# novice_shield_v1.net
KiCad netlist of a schematic drawn in EAGLE
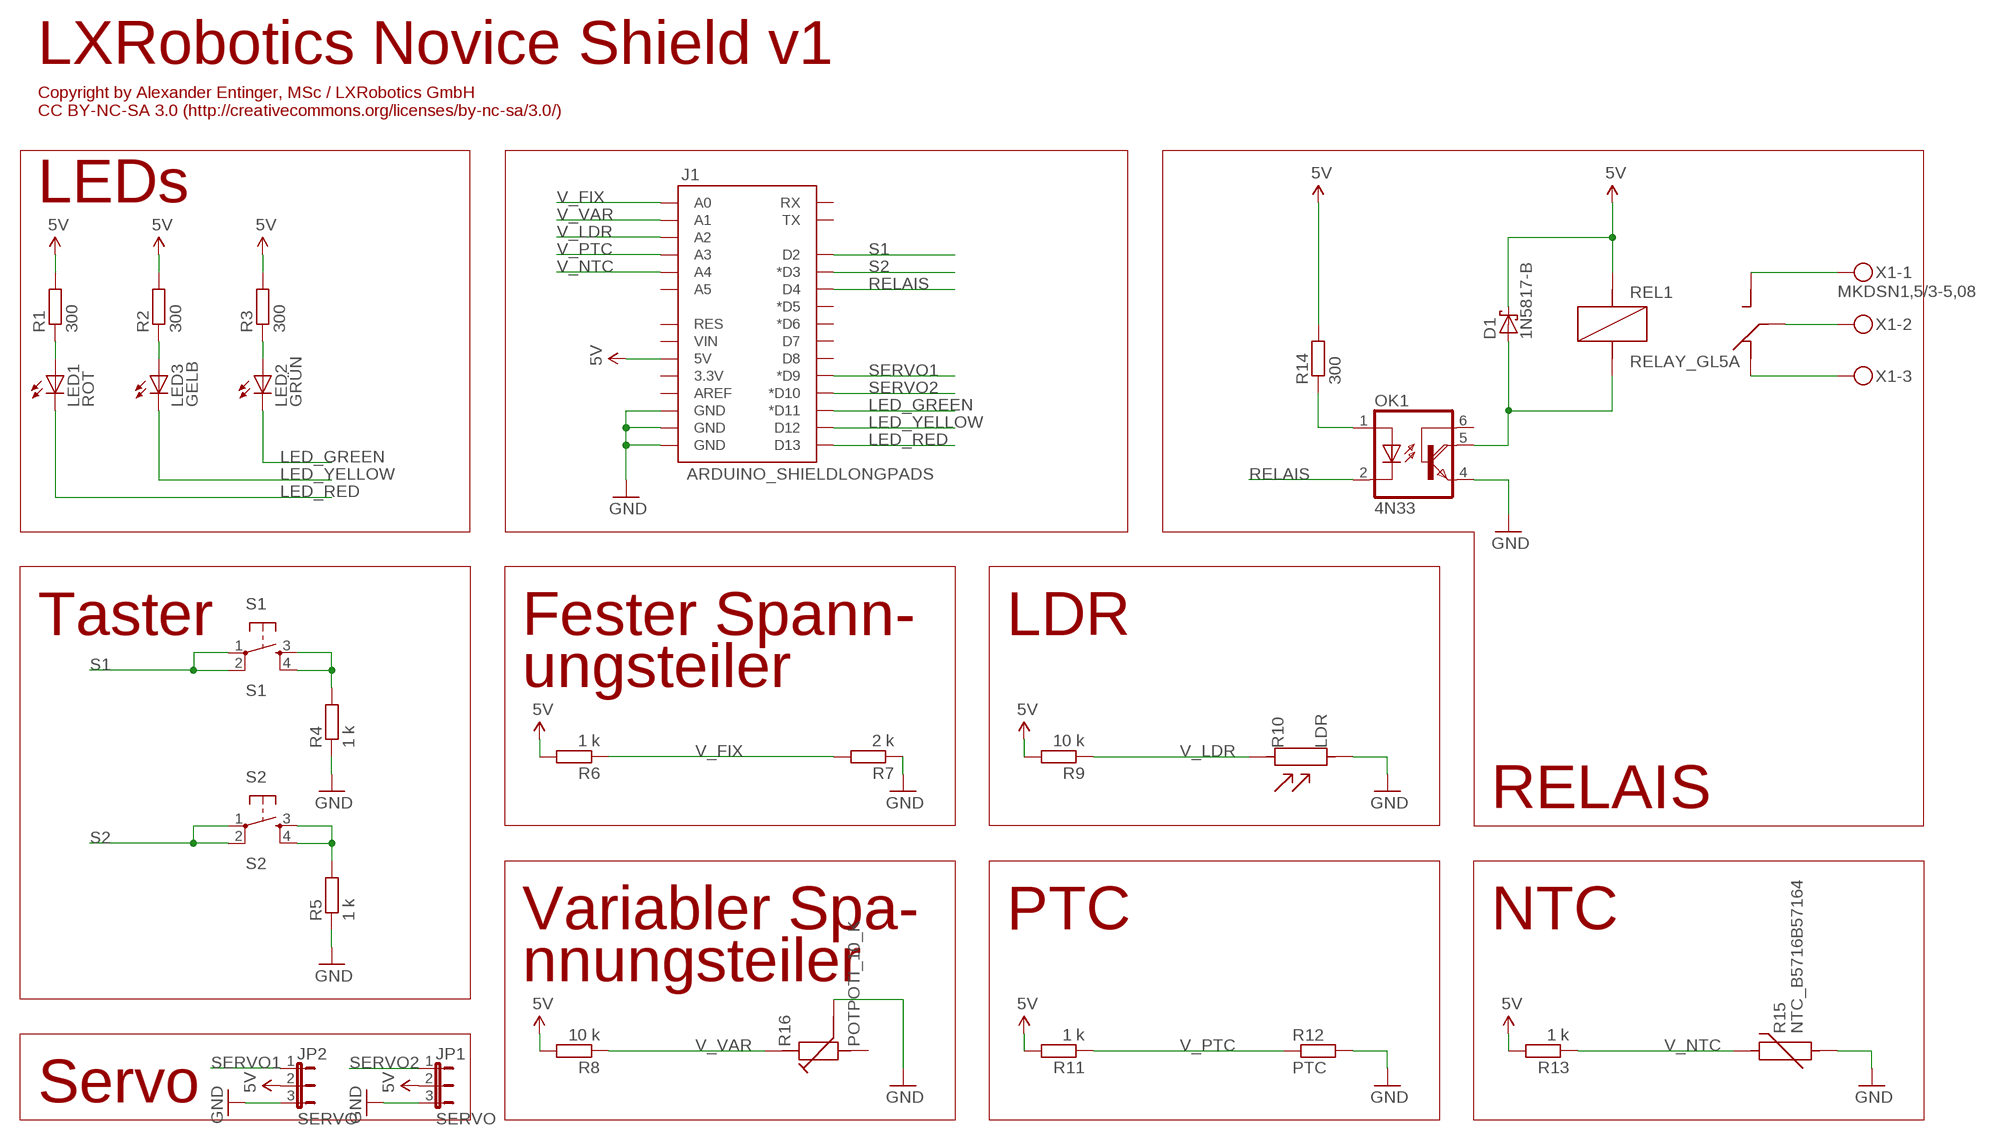
[diagram p0: schematic, sheet 1]

(export (version "E")
  (design (tool "Eeschema 10.0.6"))
  (components
    (comp (ref "D1")
      (value "1N5817-B")
      (footprint "eagle-import:DO41-7.6")
      (libsource (lib "eagle-import") (part "1N5817-B"))
    )
    (comp (ref "J1")
      (value "ARDUINO_SHIELDLONGPADS")
      (footprint "eagle-import:DUEMILANOVE_SHIELD_LONGPADS")
      (libsource (lib "eagle-import") (part "ARDUINO_SHIELDLONGPADS"))
    )
    (comp (ref "JP1")
      (value "SERVO")
      (footprint "eagle-import:JP2")
      (libsource (lib "eagle-import") (part "JP2E"))
    )
    (comp (ref "JP2")
      (value "SERVO")
      (footprint "eagle-import:JP2")
      (libsource (lib "eagle-import") (part "JP2E"))
    )
    (comp (ref "LED1")
      (value "ROT")
      (footprint "eagle-import:LED5MM")
      (libsource (lib "eagle-import") (part "LED5MM"))
    )
    (comp (ref "LED2")
      (value "GRÜN")
      (footprint "eagle-import:LED5MM")
      (libsource (lib "eagle-import") (part "LED5MM"))
    )
    (comp (ref "LED3")
      (value "GELB")
      (footprint "eagle-import:LED5MM")
      (libsource (lib "eagle-import") (part "LED5MM"))
    )
    (comp (ref "OK1")
      (value "4N33")
      (footprint "eagle-import:DIL06")
      (fields (field (name "MF") "VISHAY/TELEFUNKEN"))
      (libsource (lib "eagle-import") (part "4N33"))
    )
    (comp (ref "R1")
      (value "300")
      (footprint "eagle-import:0204_5")
      (libsource (lib "eagle-import") (part "R-EU_0204/5"))
    )
    (comp (ref "R2")
      (value "300")
      (footprint "eagle-import:0204_5")
      (libsource (lib "eagle-import") (part "R-EU_0204/5"))
    )
    (comp (ref "R3")
      (value "300")
      (footprint "eagle-import:0204_5")
      (libsource (lib "eagle-import") (part "R-EU_0204/5"))
    )
    (comp (ref "R4")
      (value "1 k")
      (footprint "eagle-import:0204_5")
      (libsource (lib "eagle-import") (part "R-EU_0204/5"))
    )
    (comp (ref "R5")
      (value "1 k")
      (footprint "eagle-import:0204_5")
      (libsource (lib "eagle-import") (part "R-EU_0204/5"))
    )
    (comp (ref "R6")
      (value "1 k")
      (footprint "eagle-import:0204_5")
      (libsource (lib "eagle-import") (part "R-EU_0204/5"))
    )
    (comp (ref "R7")
      (value "2 k")
      (footprint "eagle-import:0204_5")
      (libsource (lib "eagle-import") (part "R-EU_0204/5"))
    )
    (comp (ref "R8")
      (value "10 k")
      (footprint "eagle-import:0204_5")
      (libsource (lib "eagle-import") (part "R-EU_0204/5"))
    )
    (comp (ref "R9")
      (value "10 k")
      (footprint "eagle-import:0204_5")
      (libsource (lib "eagle-import") (part "R-EU_0204/5"))
    )
    (comp (ref "R10")
      (value "LDR")
      (footprint "eagle-import:LDR")
      (libsource (lib "eagle-import") (part "LDR"))
    )
    (comp (ref "R11")
      (value "1 k")
      (footprint "eagle-import:0204_5")
      (libsource (lib "eagle-import") (part "R-EU_0204/5"))
    )
    (comp (ref "R12")
      (value "PTC")
      (footprint "eagle-import:0207_10")
      (libsource (lib "eagle-import") (part "R-EU_0207/10"))
    )
    (comp (ref "R13")
      (value "1 k")
      (footprint "eagle-import:0204_5")
      (libsource (lib "eagle-import") (part "R-EU_0204/5"))
    )
    (comp (ref "R14")
      (value "300")
      (footprint "eagle-import:0204_5")
      (libsource (lib "eagle-import") (part "R-EU_0204/5"))
    )
    (comp (ref "R15")
      (value "NTC_B5716B57164")
      (footprint "eagle-import:NTC_5MM_RADIAL")
      (libsource (lib "eagle-import") (part "NTC_B5716B57164"))
    )
    (comp (ref "R16")
      (value "POTPOTI_10_K")
      (footprint "eagle-import:POT_10K")
      (libsource (lib "eagle-import") (part "POTPOTI_10_K"))
    )
    (comp (ref "REL1")
      (value "RELAY_GL5A")
      (footprint "eagle-import:RELAY_GL5A")
      (libsource (lib "eagle-import") (part "RELAY_GL5A"))
    )
    (comp (ref "S1")
      (value "S1")
      (footprint "eagle-import:TACTILE-PTH")
      (libsource (lib "eagle-import") (part "TAC_SWITCHPTH"))
    )
    (comp (ref "S2")
      (value "S2")
      (footprint "eagle-import:TACTILE-PTH")
      (libsource (lib "eagle-import") (part "TAC_SWITCHPTH"))
    )
    (comp (ref "X1")
      (value "MKDSN1,5/3-5,08")
      (footprint "eagle-import:MKDSN1,5_3-5,08")
      (fields (field (name "MPN") "SMKDSN1,5/3-5,08"))
      (libsource (lib "eagle-import") (part "MKDSN1,5/3-5,08"))
    )
  )
  (nets
    (net (code "1") (name "/LED_GREEN") (class "Default")
      (node (ref "J1") (pin "D11") (pinfunction "*D11_D11") (pintype "bidirectional"))
      (node (ref "LED2") (pin "K") (pinfunction "C_K") (pintype "passive"))
    )
    (net (code "2") (name "/LED_RED") (class "Default")
      (node (ref "J1") (pin "D13") (pinfunction "D13_D13") (pintype "bidirectional"))
      (node (ref "LED1") (pin "K") (pinfunction "C_K") (pintype "passive"))
    )
    (net (code "3") (name "/LED_YELLOW") (class "Default")
      (node (ref "J1") (pin "D12") (pinfunction "D12_D12") (pintype "bidirectional"))
      (node (ref "LED3") (pin "K") (pinfunction "C_K") (pintype "passive"))
    )
    (net (code "4") (name "/RELAIS") (class "Default")
      (node (ref "J1") (pin "D4") (pinfunction "D4_D4") (pintype "bidirectional"))
      (node (ref "OK1") (pin "2") (pinfunction "C_2") (pintype "passive"))
    )
    (net (code "5") (name "/S1") (class "Default")
      (node (ref "J1") (pin "D2") (pinfunction "D2_D2") (pintype "bidirectional"))
      (node (ref "S1") (pin "1") (pinfunction "1_1") (pintype "passive"))
      (node (ref "S1") (pin "2") (pinfunction "2_2") (pintype "passive"))
    )
    (net (code "6") (name "/S2") (class "Default")
      (node (ref "J1") (pin "D3") (pinfunction "*D3_D3") (pintype "bidirectional"))
      (node (ref "S2") (pin "1") (pinfunction "1_1") (pintype "passive"))
      (node (ref "S2") (pin "2") (pinfunction "2_2") (pintype "passive"))
    )
    (net (code "7") (name "/SERVO1") (class "Default")
      (node (ref "J1") (pin "D9") (pinfunction "*D9_D9") (pintype "bidirectional"))
      (node (ref "JP2") (pin "1") (pinfunction "1_1") (pintype "passive"))
    )
    (net (code "8") (name "/SERVO2") (class "Default")
      (node (ref "J1") (pin "D10") (pinfunction "*D10_D10") (pintype "bidirectional"))
      (node (ref "JP1") (pin "1") (pinfunction "1_1") (pintype "passive"))
    )
    (net (code "9") (name "/V_FIX") (class "Default")
      (node (ref "J1") (pin "A0") (pinfunction "A0_A0") (pintype "bidirectional"))
      (node (ref "R6") (pin "1") (pinfunction "1_1") (pintype "passive"))
      (node (ref "R7") (pin "2") (pinfunction "2_2") (pintype "passive"))
    )
    (net (code "10") (name "/V_LDR") (class "Default")
      (node (ref "J1") (pin "A2") (pinfunction "A2_A2") (pintype "bidirectional"))
      (node (ref "R10") (pin "P$1") (pinfunction "P$1_P$1") (pintype "bidirectional"))
      (node (ref "R9") (pin "1") (pinfunction "1_1") (pintype "passive"))
    )
    (net (code "11") (name "/V_NTC") (class "Default")
      (node (ref "J1") (pin "A4") (pinfunction "A4_A4") (pintype "bidirectional"))
      (node (ref "R13") (pin "1") (pinfunction "1_1") (pintype "passive"))
      (node (ref "R15") (pin "P$1") (pinfunction "1_P$1") (pintype "bidirectional"))
    )
    (net (code "12") (name "/V_PTC") (class "Default")
      (node (ref "J1") (pin "A3") (pinfunction "A3_A3") (pintype "bidirectional"))
      (node (ref "R11") (pin "1") (pinfunction "1_1") (pintype "passive"))
      (node (ref "R12") (pin "1") (pinfunction "1_1") (pintype "passive"))
    )
    (net (code "13") (name "/V_VAR") (class "Default")
      (node (ref "J1") (pin "A1") (pinfunction "A1_A1") (pintype "bidirectional"))
      (node (ref "R16") (pin "S") (pinfunction "S_S") (pintype "bidirectional"))
      (node (ref "R8") (pin "1") (pinfunction "1_1") (pintype "passive"))
    )
    (net (code "14") (name "5V") (class "Default")
      (node (ref "D1") (pin "C") (pinfunction "C_C") (pintype "passive"))
      (node (ref "J1") (pin "5V") (pinfunction "5V_5V") (pintype "bidirectional"))
      (node (ref "JP1") (pin "2") (pinfunction "2_2") (pintype "passive"))
      (node (ref "JP2") (pin "2") (pinfunction "2_2") (pintype "passive"))
      (node (ref "R1") (pin "2") (pinfunction "2_2") (pintype "passive"))
      (node (ref "R11") (pin "2") (pinfunction "2_2") (pintype "passive"))
      (node (ref "R13") (pin "2") (pinfunction "2_2") (pintype "passive"))
      (node (ref "R14") (pin "2") (pinfunction "2_2") (pintype "passive"))
      (node (ref "R2") (pin "2") (pinfunction "2_2") (pintype "passive"))
      (node (ref "R3") (pin "2") (pinfunction "2_2") (pintype "passive"))
      (node (ref "R6") (pin "2") (pinfunction "2_2") (pintype "passive"))
      (node (ref "R8") (pin "2") (pinfunction "2_2") (pintype "passive"))
      (node (ref "R9") (pin "2") (pinfunction "2_2") (pintype "passive"))
      (node (ref "REL1") (pin "R2") (pinfunction "R2_COIL1_R2") (pintype "bidirectional"))
    )
    (net (code "15") (name "GND") (class "Default")
      (node (ref "J1") (pin "GND@0") (pinfunction "GND_GND@0") (pintype "bidirectional"))
      (node (ref "J1") (pin "GND@1") (pinfunction "GND_GND@1") (pintype "bidirectional"))
      (node (ref "J1") (pin "GND@2") (pinfunction "GND_GND@2") (pintype "bidirectional"))
      (node (ref "JP1") (pin "3") (pinfunction "3_3") (pintype "passive"))
      (node (ref "JP2") (pin "3") (pinfunction "3_3") (pintype "passive"))
      (node (ref "OK1") (pin "4") (pinfunction "E_4") (pintype "passive"))
      (node (ref "R10") (pin "P$2") (pinfunction "P$2_P$2") (pintype "bidirectional"))
      (node (ref "R12") (pin "2") (pinfunction "2_2") (pintype "passive"))
      (node (ref "R15") (pin "P$2") (pinfunction "2_P$2") (pintype "bidirectional"))
      (node (ref "R16") (pin "VAR") (pinfunction "VAR_VAR") (pintype "bidirectional"))
      (node (ref "R4") (pin "1") (pinfunction "1_1") (pintype "passive"))
      (node (ref "R5") (pin "1") (pinfunction "1_1") (pintype "passive"))
      (node (ref "R7") (pin "1") (pinfunction "1_1") (pintype "passive"))
    )
    (net (code "16") (name "Net-(LED1-PadA)") (class "Default")
      (node (ref "LED1") (pin "A") (pinfunction "A_A") (pintype "passive"))
      (node (ref "R1") (pin "1") (pinfunction "1_1") (pintype "passive"))
    )
    (net (code "17") (name "Net-(LED2-PadA)") (class "Default")
      (node (ref "LED2") (pin "A") (pinfunction "A_A") (pintype "passive"))
      (node (ref "R3") (pin "1") (pinfunction "1_1") (pintype "passive"))
    )
    (net (code "18") (name "Net-(LED3-PadA)") (class "Default")
      (node (ref "LED3") (pin "A") (pinfunction "A_A") (pintype "passive"))
      (node (ref "R2") (pin "1") (pinfunction "1_1") (pintype "passive"))
    )
    (net (code "19") (name "Net-(OK1-A)") (class "Default")
      (node (ref "OK1") (pin "1") (pinfunction "A_1") (pintype "passive"))
      (node (ref "R14") (pin "1") (pinfunction "1_1") (pintype "passive"))
    )
    (net (code "20") (name "Net-(OK1-COL)") (class "Default")
      (node (ref "D1") (pin "A") (pinfunction "A_A") (pintype "passive"))
      (node (ref "OK1") (pin "5") (pinfunction "COL_5") (pintype "passive"))
      (node (ref "REL1") (pin "R5") (pinfunction "R5_COIL2_R5") (pintype "bidirectional"))
    )
    (net (code "21") (name "Net-(R4-Pad2)") (class "Default")
      (node (ref "R4") (pin "2") (pinfunction "2_2") (pintype "passive"))
      (node (ref "S1") (pin "3") (pinfunction "3_3") (pintype "passive"))
      (node (ref "S1") (pin "4") (pinfunction "4_4") (pintype "passive"))
    )
    (net (code "22") (name "Net-(R5-Pad2)") (class "Default")
      (node (ref "R5") (pin "2") (pinfunction "2_2") (pintype "passive"))
      (node (ref "S2") (pin "3") (pinfunction "3_3") (pintype "passive"))
      (node (ref "S2") (pin "4") (pinfunction "4_4") (pintype "passive"))
    )
    (net (code "23") (name "Net-(REL1-R1_COMMON)") (class "Default")
      (node (ref "REL1") (pin "R1") (pinfunction "R1_COMMON_R1") (pintype "bidirectional"))
      (node (ref "X1") (pin "2") (pinfunction "KL_2") (pintype "passive"))
    )
    (net (code "24") (name "Net-(REL1-R3_SW)") (class "Default")
      (node (ref "REL1") (pin "R3") (pinfunction "R3_SW_R3") (pintype "bidirectional"))
      (node (ref "X1") (pin "1") (pinfunction "KL_1") (pintype "passive"))
    )
    (net (code "25") (name "Net-(REL1-R4_SW)") (class "Default")
      (node (ref "REL1") (pin "R4") (pinfunction "R4_SW_R4") (pintype "bidirectional"))
      (node (ref "X1") (pin "3") (pinfunction "KL_3") (pintype "passive"))
    )
    (net (code "26") (name "unconnected-(J1-*D5-PadD5)") (class "Default")
      (node (ref "J1") (pin "D5") (pinfunction "*D5_D5") (pintype "bidirectional"))
    )
    (net (code "27") (name "unconnected-(J1-*D6-PadD6)") (class "Default")
      (node (ref "J1") (pin "D6") (pinfunction "*D6_D6") (pintype "bidirectional"))
    )
    (net (code "28") (name "unconnected-(J1-Pad3.3V)") (class "Default")
      (node (ref "J1") (pin "3.3V") (pinfunction "3.3V_3.3V") (pintype "bidirectional"))
    )
    (net (code "29") (name "unconnected-(J1-PadA5)") (class "Default")
      (node (ref "J1") (pin "A5") (pinfunction "A5_A5") (pintype "bidirectional"))
    )
    (net (code "30") (name "unconnected-(J1-PadAREF)") (class "Default")
      (node (ref "J1") (pin "AREF") (pinfunction "AREF_AREF") (pintype "bidirectional"))
    )
    (net (code "31") (name "unconnected-(J1-PadD7)") (class "Default")
      (node (ref "J1") (pin "D7") (pinfunction "D7_D7") (pintype "bidirectional"))
    )
    (net (code "32") (name "unconnected-(J1-PadD8)") (class "Default")
      (node (ref "J1") (pin "D8") (pinfunction "D8_D8") (pintype "bidirectional"))
    )
    (net (code "33") (name "unconnected-(J1-PadRES)") (class "Default")
      (node (ref "J1") (pin "RES") (pinfunction "RES_RES") (pintype "bidirectional"))
    )
    (net (code "34") (name "unconnected-(J1-PadRX)") (class "Default")
      (node (ref "J1") (pin "RX") (pinfunction "RX_RX") (pintype "bidirectional"))
    )
    (net (code "35") (name "unconnected-(J1-PadTX)") (class "Default")
      (node (ref "J1") (pin "TX") (pinfunction "TX_TX") (pintype "bidirectional"))
    )
    (net (code "36") (name "unconnected-(J1-PadVIN)") (class "Default")
      (node (ref "J1") (pin "VIN") (pinfunction "VIN_VIN") (pintype "bidirectional"))
    )
    (net (code "37") (name "unconnected-(OK1-B-Pad6)") (class "Default")
      (node (ref "OK1") (pin "6") (pinfunction "B_6") (pintype "passive"))
    )
    (net (code "38") (name "unconnected-(R16-PadE)") (class "Default")
      (node (ref "R16") (pin "E") (pinfunction "E_E") (pintype "bidirectional"))
    )
  )
)
